# leo_DM_BUCK.net
KiCad netlist of a schematic drawn in Altium Designer
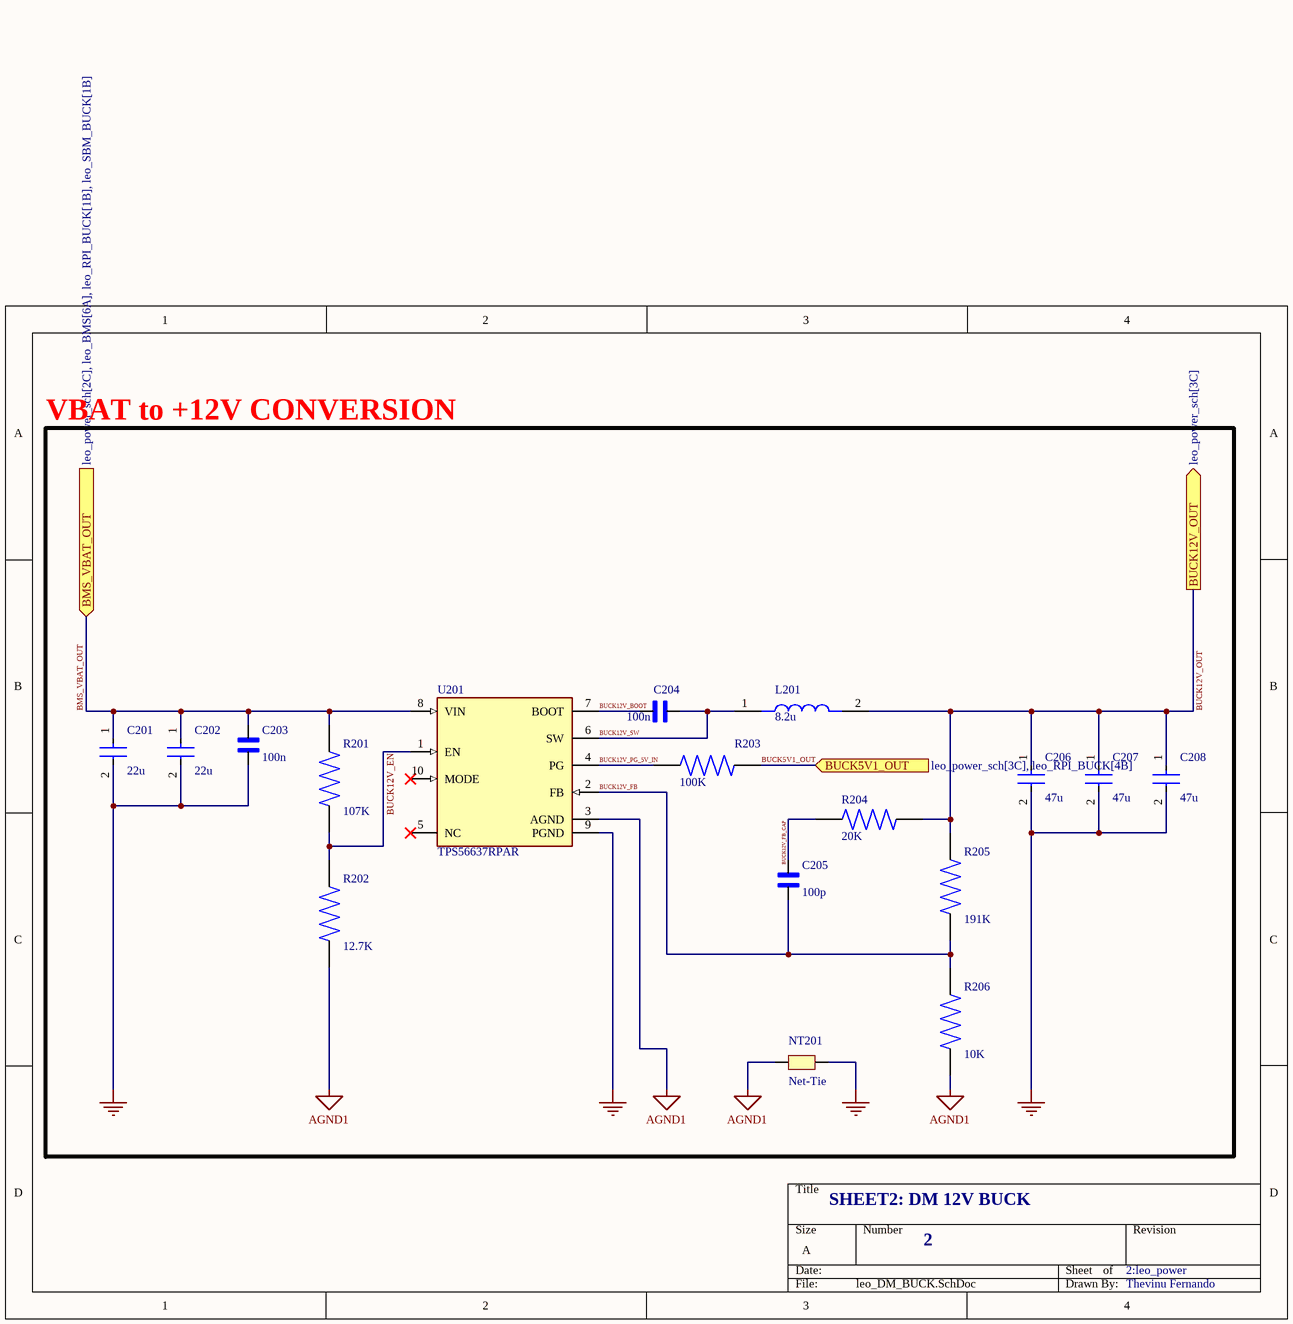
[diagram p0: leo_DM_BUCK.SchDoc]

(export (version "E")
  (design (tool "Eeschema 10.0.6"))
  (components
    (comp (ref "C201")
      (value "22u")
      (footprint "CAP_1206")
      (fields
        (field (name "MOUSER PART NUMBER") "187-CL31A226KAHNNNE")
        (field (name "PART NUMBER") "CL31A226KAHNNNE")
        (field (name "DIGIKEY PART NUMBER") "1276-3047-1-ND")
      )
      (libsource (lib "leo_power_schlib") (part "CAP_1206"))
    )
    (comp (ref "C202")
      (value "22u")
      (footprint "CAP_1206")
      (fields
        (field (name "MOUSER PART NUMBER") "187-CL31A226KAHNNNE")
        (field (name "PART NUMBER") "CL31A226KAHNNNE")
        (field (name "DIGIKEY PART NUMBER") "1276-3047-1-ND")
      )
      (libsource (lib "leo_power_schlib") (part "CAP_1206"))
    )
    (comp (ref "C203")
      (value "100n")
      (footprint "CAP_0603")
      (description "Â±10% 50V Ceramic Capacitor X7R 0603 (1608 Metric)")
      (fields (field (name "MF") "Samsung Electro-Mechanics") (field (name "MP") "CL10B104KB8NNNC"))
      (libsource (lib "leo_power_schlib") (part "CAP_0603"))
    )
    (comp (ref "C204")
      (value "100n")
      (footprint "CAP_0402")
      (description "±10% 50V Ceramic Capacitor X7R 0402")
      (fields (field (name "MF") "Samsung") (field (name "MP") "CL05B104KO5NNNC"))
      (libsource (lib "") (part "CAP_0402_1"))
    )
    (comp (ref "C205")
      (value "100p")
      (footprint "CAP_0402")
      (description "±10% 50V Ceramic Capacitor X7R 0402")
      (fields (field (name "MF") "Samsung") (field (name "MP") "CL05B104KO5NNNC"))
      (libsource (lib "leo_power_schlib") (part "CAP_0402"))
    )
    (comp (ref "C206")
      (value "47u")
      (footprint "CAP_1206")
      (fields
        (field (name "MOUSER PART NUMBER") "187-CL31A226KAHNNNE")
        (field (name "PART NUMBER") "CL31A226KAHNNNE")
        (field (name "DIGIKEY PART NUMBER") "1276-3047-1-ND")
      )
      (libsource (lib "leo_power_schlib") (part "CAP_1206"))
    )
    (comp (ref "C207")
      (value "47u")
      (footprint "CAP_1206")
      (fields
        (field (name "MOUSER PART NUMBER") "187-CL31A226KAHNNNE")
        (field (name "PART NUMBER") "CL31A226KAHNNNE")
        (field (name "DIGIKEY PART NUMBER") "1276-3047-1-ND")
      )
      (libsource (lib "leo_power_schlib") (part "CAP_1206"))
    )
    (comp (ref "C208")
      (value "47u")
      (footprint "CAP_1206")
      (fields
        (field (name "MOUSER PART NUMBER") "187-CL31A226KAHNNNE")
        (field (name "PART NUMBER") "CL31A226KAHNNNE")
        (field (name "DIGIKEY PART NUMBER") "1276-3047-1-ND")
      )
      (libsource (lib "leo_power_schlib") (part "CAP_1206"))
    )
    (comp (ref "L201")
      (value "8.2u")
      (footprint "IND_104CDMCCDS-8R2MC")
      (description "Inductor Power Shielded/Molded Wirewound 8.2uH 20% 100KHz Metal 8.3A 0.027Ohm DCR 4040 T/R")
      (fields (field (name "MF") "Sumida") (field (name "MP") "104CDMCCDS-8R2MC"))
      (libsource (lib "leo_power_schlib") (part "104CDMCCDS-8R2MC"))
    )
    (comp (ref "NT201")
      (value "Net-Tie")
      (footprint "NET-TIE_SMD")
      (description "Single point connection between nets.")
      (libsource (lib "leo_power_schlib") (part "NET-TIE"))
    )
    (comp (ref "R201")
      (value "107K")
      (footprint "RES_0603")
      (description "Â±1% 0.1W, 1/10W Chip Resistor 0603 (1608 Metric) Moisture Resistant Thick Film")
      (fields (field (name "MF") "Yageo") (field (name "MP") "RC0603FR-0791KL"))
      (libsource (lib "leo_power_schlib") (part "RES_0603"))
    )
    (comp (ref "R202")
      (value "12.7K")
      (footprint "RES_0603")
      (description "Â±1% 0.1W, 1/10W Chip Resistor 0603 (1608 Metric) Moisture Resistant Thick Film")
      (fields (field (name "MF") "Yageo") (field (name "MP") "RC0603FR-0791KL"))
      (libsource (lib "leo_power_schlib") (part "RES_0603"))
    )
    (comp (ref "R203")
      (value "100K")
      (footprint "RES_0402")
      (description "Chip Resistor 0402 (1005 Metric) Automotive AEC-Q200 Thick Film")
      (fields (field (name "MF") "Panasonic") (field (name "MP") "ERJ-2RKF1002X"))
      (libsource (lib "leo_power_schlib") (part "RES_0402"))
    )
    (comp (ref "R204")
      (value "20K")
      (footprint "RES_0402")
      (description "Chip Resistor 0402 (1005 Metric) Automotive AEC-Q200 Thick Film")
      (fields (field (name "MF") "Panasonic") (field (name "MP") "ERJ-2RKF1002X"))
      (libsource (lib "leo_power_schlib") (part "RES_0402"))
    )
    (comp (ref "R205")
      (value "191K")
      (footprint "RES_0603")
      (description "Â±1% 0.1W, 1/10W Chip Resistor 0603 (1608 Metric) Moisture Resistant Thick Film")
      (fields (field (name "MF") "Yageo") (field (name "MP") "RC0603FR-0791KL"))
      (libsource (lib "leo_power_schlib") (part "RES_0603"))
    )
    (comp (ref "R206")
      (value "10K")
      (footprint "RES_0603")
      (description "Â±1% 0.1W, 1/10W Chip Resistor 0603 (1608 Metric) Moisture Resistant Thick Film")
      (fields (field (name "MF") "Yageo") (field (name "MP") "RC0603FR-0791KL"))
      (libsource (lib "leo_power_schlib") (part "RES_0603"))
    )
    (comp (ref "U201")
      (value "TPS56637RPAR")
      (footprint "FP-RPA0010A-MFG")
      (description "Buck Switching Regulator IC Adjustable 0.6V~13V 1 Output 6A VQFN-10-HR(3x3)")
      (fields
        (field (name "OCTOPART") "https://octopart.com/tps56637rpar-texas+instruments-97650653")
        (field (name "MANUFACTURER") "Texas Instruments")
      )
      (libsource (lib "leo_power_schlib") (part "TPS56637RPAR"))
    )
  )
  (nets
    (net (code "1") (name "/BMS_VBAT_OUT") (class "Default")
      (node (ref "C201") (pin "1") (pinfunction "1_1") (pintype "passive"))
      (node (ref "C202") (pin "1") (pinfunction "1_1") (pintype "passive"))
      (node (ref "C203") (pin "2") (pinfunction "2_2") (pintype "passive"))
      (node (ref "R201") (pin "2") (pinfunction "2_2") (pintype "passive"))
      (node (ref "U201") (pin "8") (pinfunction "VIN_8") (pintype "input"))
    )
    (net (code "2") (name "/BUCK5V1_OUT") (class "Default")
      (node (ref "R203") (pin "1") (pinfunction "1_1") (pintype "passive"))
    )
    (net (code "3") (name "/BUCK12V_BOOT") (class "Default")
      (node (ref "C204") (pin "1") (pinfunction "1_1") (pintype "passive"))
      (node (ref "U201") (pin "7") (pinfunction "BOOT_7") (pintype "power_in"))
    )
    (net (code "4") (name "/BUCK12V_EN") (class "Default")
      (node (ref "R201") (pin "1") (pinfunction "1_1") (pintype "passive"))
      (node (ref "R202") (pin "2") (pinfunction "2_2") (pintype "passive"))
      (node (ref "U201") (pin "1") (pinfunction "EN_1") (pintype "input"))
    )
    (net (code "5") (name "/BUCK12V_FB") (class "Default")
      (node (ref "C205") (pin "1") (pinfunction "1_1") (pintype "passive"))
      (node (ref "R205") (pin "1") (pinfunction "1_1") (pintype "passive"))
      (node (ref "R206") (pin "2") (pinfunction "2_2") (pintype "passive"))
      (node (ref "U201") (pin "2") (pinfunction "FB_2") (pintype "input"))
    )
    (net (code "6") (name "/BUCK12V_FB_CAP") (class "Default")
      (node (ref "C205") (pin "2") (pinfunction "2_2") (pintype "passive"))
      (node (ref "R204") (pin "2") (pinfunction "2_2") (pintype "passive"))
    )
    (net (code "7") (name "/BUCK12V_OUT") (class "Default")
      (node (ref "C206") (pin "1") (pinfunction "1_1") (pintype "passive"))
      (node (ref "C207") (pin "1") (pinfunction "1_1") (pintype "passive"))
      (node (ref "C208") (pin "1") (pinfunction "1_1") (pintype "passive"))
      (node (ref "L201") (pin "2") (pinfunction "2_2") (pintype "passive"))
      (node (ref "R204") (pin "1") (pinfunction "1_1") (pintype "passive"))
      (node (ref "R205") (pin "2") (pinfunction "2_2") (pintype "passive"))
    )
    (net (code "8") (name "/BUCK12V_PG_5V_IN") (class "Default")
      (node (ref "R203") (pin "2") (pinfunction "2_2") (pintype "passive"))
      (node (ref "U201") (pin "4") (pinfunction "PG_4") (pintype "open_collector"))
    )
    (net (code "9") (name "/BUCK12V_SW") (class "Default")
      (node (ref "C204") (pin "2") (pinfunction "2_2") (pintype "passive"))
      (node (ref "L201") (pin "1") (pinfunction "1_1") (pintype "passive"))
      (node (ref "U201") (pin "6") (pinfunction "SW_6") (pintype "power_in"))
    )
    (net (code "10") (name "AGND1") (class "Default")
      (node (ref "NT201") (pin "2") (pinfunction "2_2") (pintype "passive"))
      (node (ref "R202") (pin "1") (pinfunction "1_1") (pintype "passive"))
      (node (ref "R206") (pin "1") (pinfunction "1_1") (pintype "passive"))
      (node (ref "U201") (pin "3") (pinfunction "AGND_3") (pintype "power_in"))
    )
    (net (code "11") (name "GND") (class "Default")
      (node (ref "C201") (pin "2") (pinfunction "2_2") (pintype "passive"))
      (node (ref "C202") (pin "2") (pinfunction "2_2") (pintype "passive"))
      (node (ref "C203") (pin "1") (pinfunction "1_1") (pintype "passive"))
      (node (ref "C206") (pin "2") (pinfunction "2_2") (pintype "passive"))
      (node (ref "C207") (pin "2") (pinfunction "2_2") (pintype "passive"))
      (node (ref "C208") (pin "2") (pinfunction "2_2") (pintype "passive"))
      (node (ref "NT201") (pin "1") (pinfunction "1_1") (pintype "passive"))
      (node (ref "U201") (pin "9") (pinfunction "PGND_9") (pintype "power_in"))
    )
    (net (code "12") (name "unconnected-(U201-MODE-Pad10)") (class "Default")
      (node (ref "U201") (pin "10") (pinfunction "MODE_10") (pintype "input+no_connect"))
    )
    (net (code "13") (name "unconnected-(U201-NC-Pad5)") (class "Default")
      (node (ref "U201") (pin "5") (pinfunction "NC_5") (pintype "passive+no_connect"))
    )
  )
)
